# ProPrj___2025-03-19.net
KiCad netlist of a schematic drawn in EasyEDA Pro
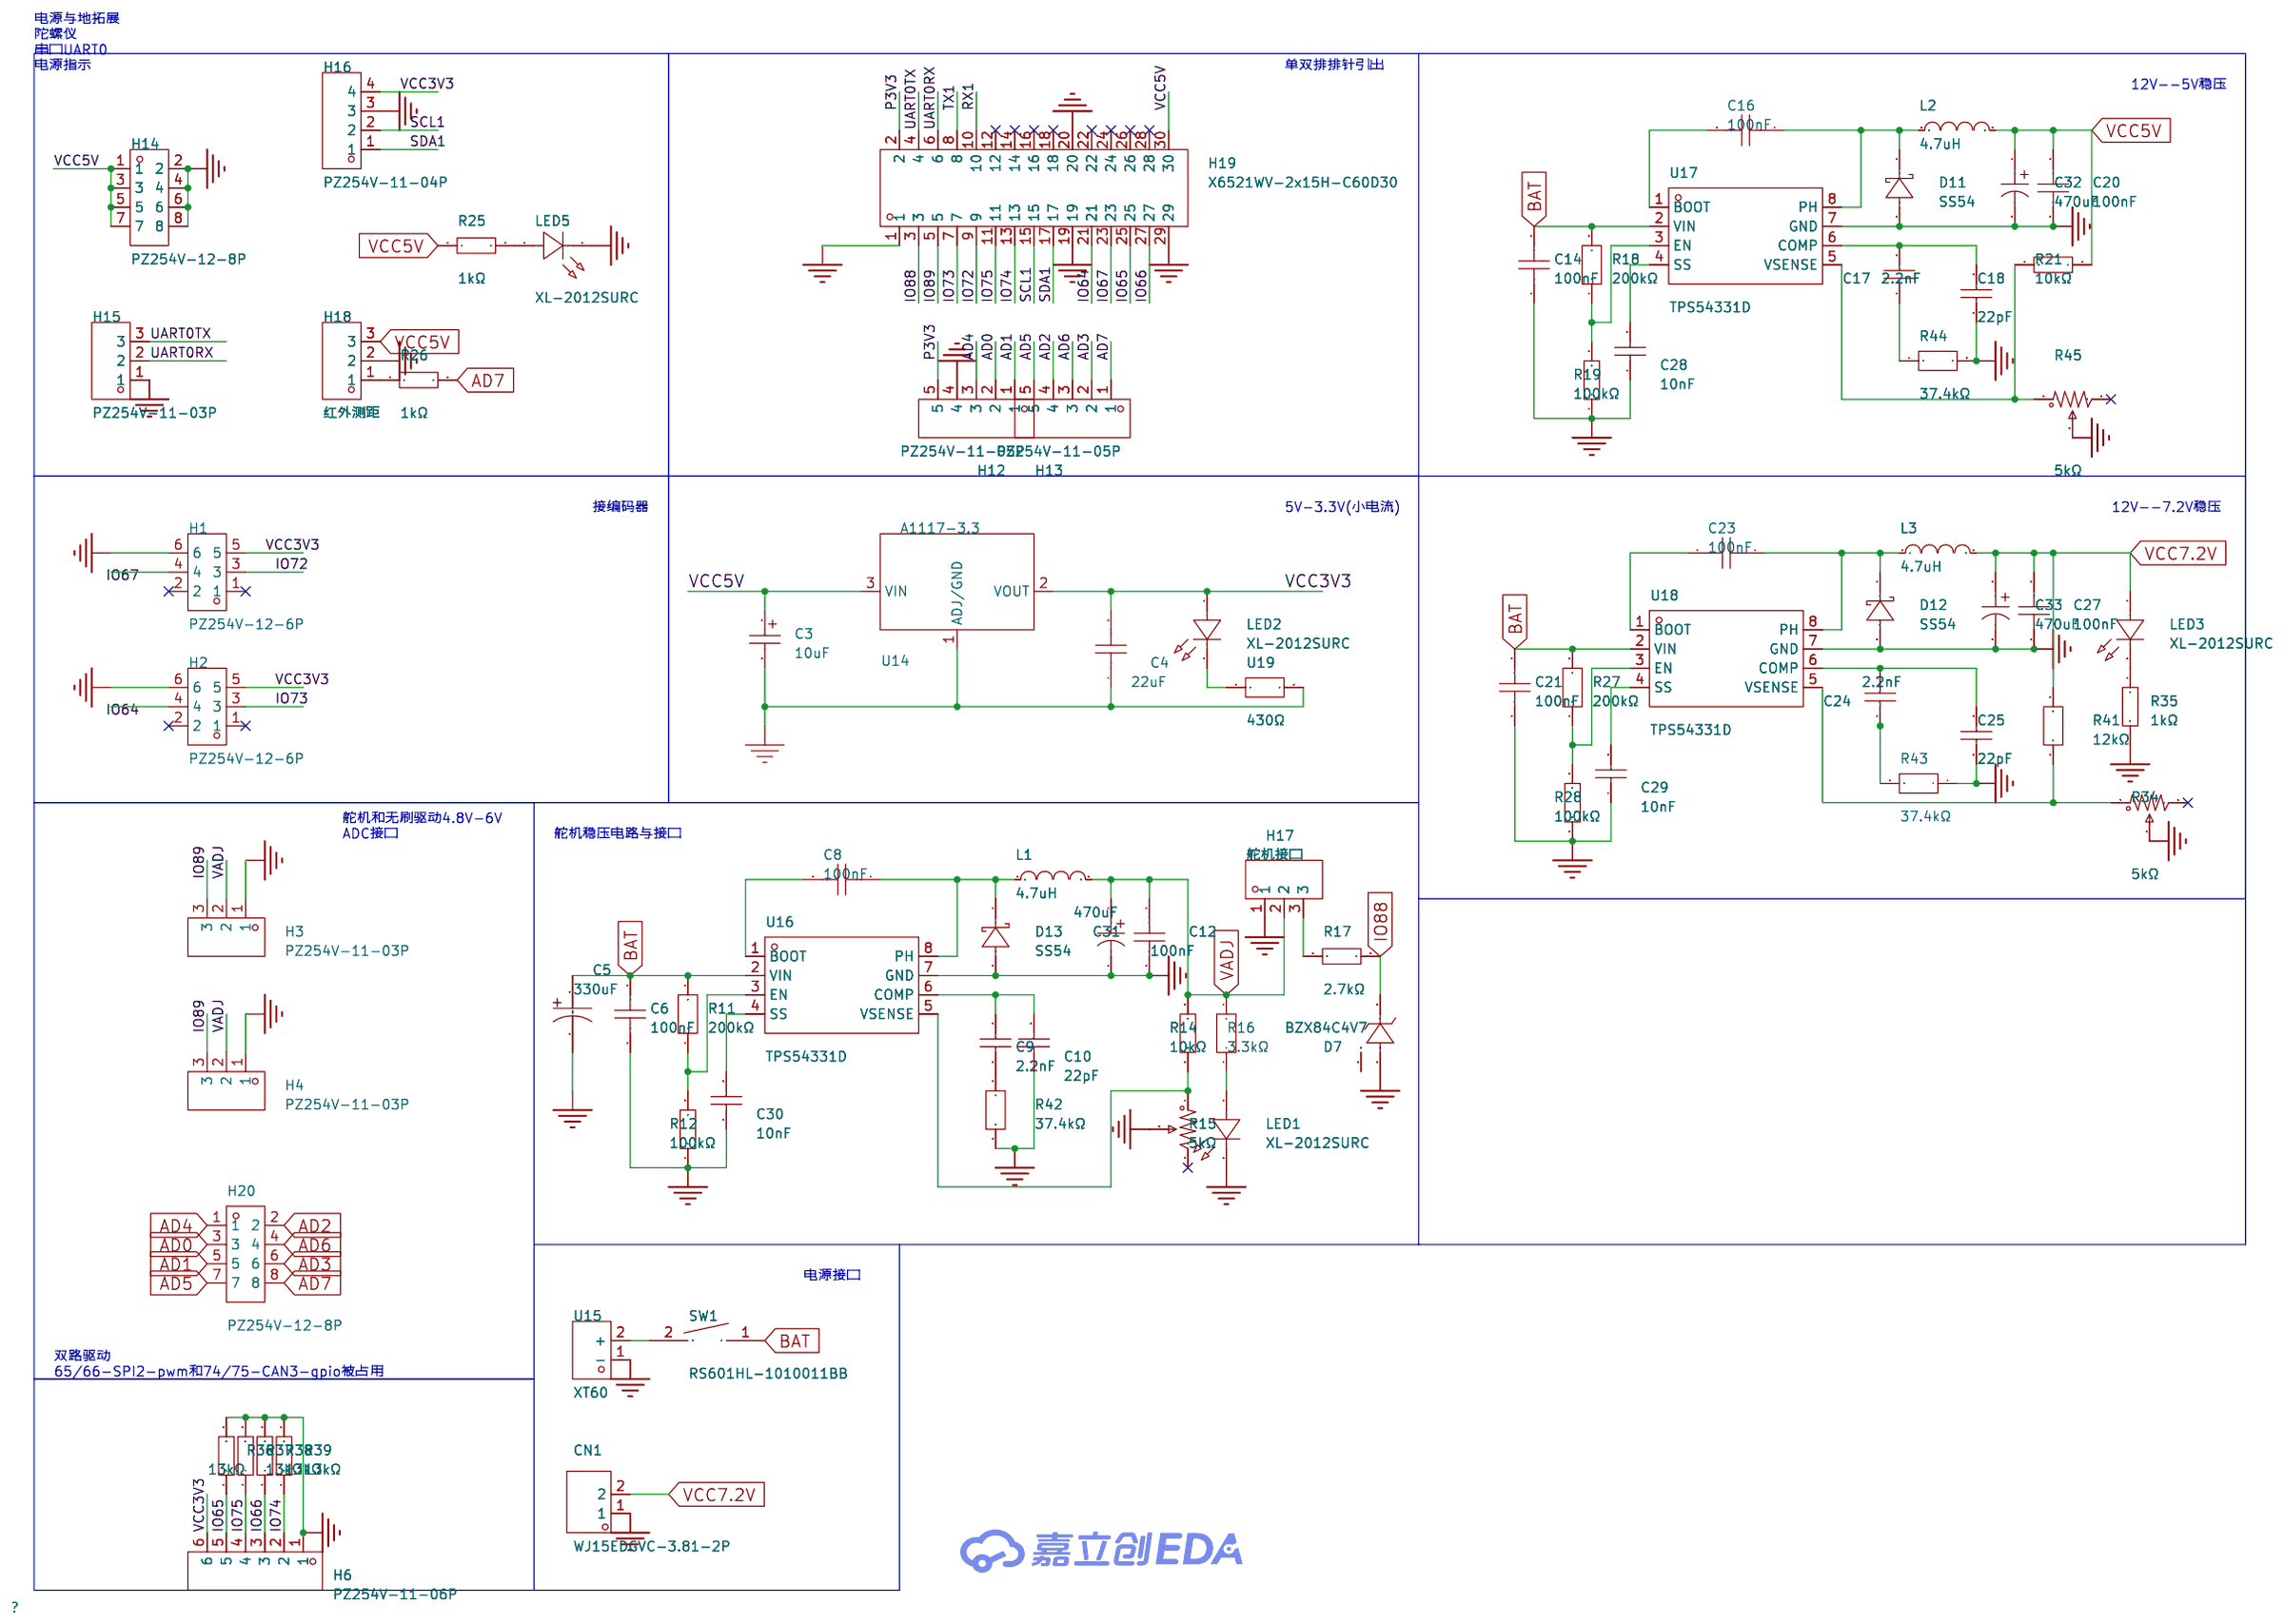
[diagram p0: schematic sheet]

(export (version "E")
  (design (tool "Eeschema 10.0.6"))
  (components
    (comp (ref "C3")
      (value "10uF")
      (footprint "easyedapro:CAP-SMD_L6.0-W3.2")
      (description "容值:10uF;精度:±10%;额定电压:16V;等效串联电阻:2Ω@100kHz;")
      (fields (field (name "Manufacturer Part") "TAJC106K016RNJ") (field (name "Manufacturer") "Kyocera AVX"))
      (libsource (lib "easyedapro") (part "TAJC106K016RNJ"))
    )
    (comp (ref "C4")
      (value "22uF")
      (footprint "easyedapro:C0805")
      (description "容值:22uF;精度:±20%;额定电压:35V;材质(温度系数):X5R;")
      (fields
        (field (name "Manufacturer Part") "CGA0805X5R226M350MT")
        (field (name "Manufacturer") "HRE(芯声)")
      )
      (libsource (lib "easyedapro") (part "CGA0805X5R226M350MT"))
    )
    (comp (ref "C5")
      (value "330uF")
      (footprint "easyedapro:CAP-SMD_BD8.0-L8.3-W8.3-LS9.3-FD-1")
      (description "容值:330uF;精度:±20%;额定电压:25V;纹波电流:228mA@120Hz;等效串联电阻(ESR):-;")
      (fields (field (name "Manufacturer Part") "RVT1E331M0810") (field (name "Manufacturer") "ROQANG(容强)"))
      (libsource (lib "easyedapro") (part "RVT1E331M0810_C335985"))
    )
    (comp (ref "C6")
      (value "100nF")
      (footprint "easyedapro:C0805")
      (description "容值:100nF;精度:±10%;额定电压:50V;材质(温度系数):X7R;")
      (fields
        (field (name "Manufacturer Part") "CC0805KRX7R9BB104")
        (field (name "Manufacturer") "YAGEO(国巨)")
      )
      (libsource (lib "easyedapro") (part "CC0805KRX7R9BB104"))
    )
    (comp (ref "C8")
      (value "100nF")
      (footprint "easyedapro:C0805")
      (description "容值:100nF;精度:±10%;额定电压:50V;材质(温度系数):X7R;")
      (fields
        (field (name "Manufacturer Part") "CC0805KRX7R9BB104")
        (field (name "Manufacturer") "YAGEO(国巨)")
      )
      (libsource (lib "easyedapro") (part "CC0805KRX7R9BB104"))
    )
    (comp (ref "C9")
      (value "2.2nF")
      (footprint "easyedapro:C0805")
      (description "容值:2.2nF;精度:±5%;额定电压:50V;材质(温度系数):C0G;")
      (fields
        (field (name "Manufacturer Part") "CL21C222JBFNNNE")
        (field (name "Manufacturer") "SAMSUNG(三星)")
      )
      (libsource (lib "easyedapro") (part "CL21C222JBFNNNE"))
    )
    (comp (ref "C10")
      (value "22pF")
      (footprint "easyedapro:C0603")
      (description "容值:22pF;精度:±5%;额定电压:50V;材质(温度系数):NP0;")
      (fields
        (field (name "Manufacturer Part") "CC0603JRNPO9BN220")
        (field (name "Manufacturer") "YAGEO(国巨)")
      )
      (libsource (lib "easyedapro") (part "CC0603JRNPO9BN220"))
    )
    (comp (ref "C12")
      (value "100nF")
      (footprint "easyedapro:C0805")
      (description "容值:100nF;精度:±10%;额定电压:50V;材质(温度系数):X7R;")
      (fields
        (field (name "Manufacturer Part") "CC0805KRX7R9BB104")
        (field (name "Manufacturer") "YAGEO(国巨)")
      )
      (libsource (lib "easyedapro") (part "CC0805KRX7R9BB104"))
    )
    (comp (ref "C14")
      (value "100nF")
      (footprint "easyedapro:C0805")
      (description "容值:100nF;精度:±10%;额定电压:50V;材质(温度系数):X7R;")
      (fields
        (field (name "Manufacturer Part") "CC0805KRX7R9BB104")
        (field (name "Manufacturer") "YAGEO(国巨)")
      )
      (libsource (lib "easyedapro") (part "CC0805KRX7R9BB104"))
    )
    (comp (ref "C16")
      (value "100nF")
      (footprint "easyedapro:C0805")
      (description "容值:100nF;精度:±10%;额定电压:50V;材质(温度系数):X7R;")
      (fields
        (field (name "Manufacturer Part") "CC0805KRX7R9BB104")
        (field (name "Manufacturer") "YAGEO(国巨)")
      )
      (libsource (lib "easyedapro") (part "CC0805KRX7R9BB104"))
    )
    (comp (ref "C17")
      (value "2.2nF")
      (footprint "easyedapro:C0805")
      (description "容值:2.2nF;精度:±5%;额定电压:50V;材质(温度系数):C0G;")
      (fields
        (field (name "Manufacturer Part") "CL21C222JBFNNNE")
        (field (name "Manufacturer") "SAMSUNG(三星)")
      )
      (libsource (lib "easyedapro") (part "CL21C222JBFNNNE"))
    )
    (comp (ref "C18")
      (value "22pF")
      (footprint "easyedapro:C0603")
      (description "容值:22pF;精度:±5%;额定电压:50V;材质(温度系数):NP0;")
      (fields
        (field (name "Manufacturer Part") "CC0603JRNPO9BN220")
        (field (name "Manufacturer") "YAGEO(国巨)")
      )
      (libsource (lib "easyedapro") (part "CC0603JRNPO9BN220"))
    )
    (comp (ref "C20")
      (value "100nF")
      (footprint "easyedapro:C0805")
      (description "容值:100nF;精度:±10%;额定电压:50V;材质(温度系数):X7R;")
      (fields
        (field (name "Manufacturer Part") "CC0805KRX7R9BB104")
        (field (name "Manufacturer") "YAGEO(国巨)")
      )
      (libsource (lib "easyedapro") (part "CC0805KRX7R9BB104"))
    )
    (comp (ref "C21")
      (value "100nF")
      (footprint "easyedapro:C0805")
      (description "容值:100nF;精度:±10%;额定电压:50V;材质(温度系数):X7R;")
      (fields
        (field (name "Manufacturer Part") "CC0805KRX7R9BB104")
        (field (name "Manufacturer") "YAGEO(国巨)")
      )
      (libsource (lib "easyedapro") (part "CC0805KRX7R9BB104"))
    )
    (comp (ref "C23")
      (value "100nF")
      (footprint "easyedapro:C0805")
      (description "容值:100nF;精度:±10%;额定电压:50V;材质(温度系数):X7R;")
      (fields
        (field (name "Manufacturer Part") "CC0805KRX7R9BB104")
        (field (name "Manufacturer") "YAGEO(国巨)")
      )
      (libsource (lib "easyedapro") (part "CC0805KRX7R9BB104"))
    )
    (comp (ref "C24")
      (value "2.2nF")
      (footprint "easyedapro:C0805")
      (description "容值:2.2nF;精度:±5%;额定电压:50V;材质(温度系数):C0G;")
      (fields
        (field (name "Manufacturer Part") "CL21C222JBFNNNE")
        (field (name "Manufacturer") "SAMSUNG(三星)")
      )
      (libsource (lib "easyedapro") (part "CL21C222JBFNNNE"))
    )
    (comp (ref "C25")
      (value "22pF")
      (footprint "easyedapro:C0603")
      (description "容值:22pF;精度:±5%;额定电压:50V;材质(温度系数):NP0;")
      (fields
        (field (name "Manufacturer Part") "CC0603JRNPO9BN220")
        (field (name "Manufacturer") "YAGEO(国巨)")
      )
      (libsource (lib "easyedapro") (part "CC0603JRNPO9BN220"))
    )
    (comp (ref "C27")
      (value "100nF")
      (footprint "easyedapro:C0805")
      (description "容值:100nF;精度:±10%;额定电压:50V;材质(温度系数):X7R;")
      (fields
        (field (name "Manufacturer Part") "CC0805KRX7R9BB104")
        (field (name "Manufacturer") "YAGEO(国巨)")
      )
      (libsource (lib "easyedapro") (part "CC0805KRX7R9BB104"))
    )
    (comp (ref "C28")
      (value "10nF")
      (footprint "easyedapro:C0805")
      (description "容值:10nF;精度:±10%;额定电压:50V;材质(温度系数):X7R;")
      (fields
        (field (name "Manufacturer Part") "CL21B103KBANNNC")
        (field (name "Manufacturer") "SAMSUNG(三星)")
      )
      (libsource (lib "easyedapro") (part "CL21B103KBANNNC"))
    )
    (comp (ref "C29")
      (value "10nF")
      (footprint "easyedapro:C0805")
      (description "容值:10nF;精度:±10%;额定电压:50V;材质(温度系数):X7R;")
      (fields
        (field (name "Manufacturer Part") "CL21B103KBANNNC")
        (field (name "Manufacturer") "SAMSUNG(三星)")
      )
      (libsource (lib "easyedapro") (part "CL21B103KBANNNC"))
    )
    (comp (ref "C30")
      (value "10nF")
      (footprint "easyedapro:C0805")
      (description "容值:10nF;精度:±10%;额定电压:50V;材质(温度系数):X7R;")
      (fields
        (field (name "Manufacturer Part") "CL21B103KBANNNC")
        (field (name "Manufacturer") "SAMSUNG(三星)")
      )
      (libsource (lib "easyedapro") (part "CL21B103KBANNNC"))
    )
    (comp (ref "C31")
      (value "470uF")
      (footprint "easyedapro:CAP-SMD_BD8.0-L8.3-W8.3-LS8.9-FD")
      (description "容值:470uF;精度:±20%;额定电压:16V;纹波电流:240mA@120Hz;")
      (fields (field (name "Manufacturer Part") "CK1C471M-CRF10") (field (name "Manufacturer") "ROQANG(容强)"))
      (libsource (lib "easyedapro") (part "CK1C471M-CRF10_C5162359"))
    )
    (comp (ref "C32")
      (value "470uF")
      (footprint "easyedapro:CAP-SMD_BD8.0-L8.3-W8.3-LS8.9-FD")
      (description "容值:470uF;精度:±20%;额定电压:16V;纹波电流:240mA@120Hz;")
      (fields (field (name "Manufacturer Part") "CK1C471M-CRF10") (field (name "Manufacturer") "ROQANG(容强)"))
      (libsource (lib "easyedapro") (part "CK1C471M-CRF10_C5162359"))
    )
    (comp (ref "C33")
      (value "470uF")
      (footprint "easyedapro:CAP-SMD_BD8.0-L8.3-W8.3-LS8.9-FD")
      (description "容值:470uF;精度:±20%;额定电压:16V;纹波电流:240mA@120Hz;")
      (fields (field (name "Manufacturer Part") "CK1C471M-CRF10") (field (name "Manufacturer") "ROQANG(容强)"))
      (libsource (lib "easyedapro") (part "CK1C471M-CRF10_C5162359"))
    )
    (comp (ref "CN1")
      (value "WJ15EDGVC-3.81-2P")
      (footprint "easyedapro:CONN-TH_WJ15EDGVC-3.81-2P")
      (fields (field (name "Manufacturer") "KANGNEX(康奈克斯电气)"))
      (libsource (lib "easyedapro") (part "WJ15EDGVC-3.81-2P"))
    )
    (comp (ref "D7")
      (value "BZX84C4V7")
      (footprint "easyedapro:SOT-23-3_L2.9-W1.3-P1.90-LS2.4-BR")
      (description "二极管配置:独立式;稳压值(标称值):4.7V;稳压值(范围):4.4V~5V;耗散功率(Pd):350mW;")
      (fields (field (name "Manufacturer") "LGE(鲁光)"))
      (libsource (lib "easyedapro") (part "BZX84C4V7_C841158"))
    )
    (comp (ref "D11")
      (value "SS54")
      (footprint "easyedapro:SMA_L4.3-W2.6-LS5.0-RD")
      (description "二极管配置:独立式;正向压降(Vf):550mV@5A;直流反向耐压(Vr):40V;整流电流:5A;")
      (fields (field (name "Manufacturer") "TWGMC(台湾迪嘉)"))
      (libsource (lib "easyedapro") (part "SS54_C727065"))
    )
    (comp (ref "D12")
      (value "SS54")
      (footprint "easyedapro:SMA_L4.3-W2.6-LS5.0-RD")
      (description "二极管配置:独立式;正向压降(Vf):550mV@5A;直流反向耐压(Vr):40V;整流电流:5A;")
      (fields (field (name "Manufacturer") "TWGMC(台湾迪嘉)"))
      (libsource (lib "easyedapro") (part "SS54_C727065"))
    )
    (comp (ref "D13")
      (value "SS54")
      (footprint "easyedapro:SMA_L4.3-W2.6-LS5.0-RD")
      (description "二极管配置:独立式;正向压降(Vf):550mV@5A;直流反向耐压(Vr):40V;整流电流:5A;")
      (fields (field (name "Manufacturer") "TWGMC(台湾迪嘉)"))
      (libsource (lib "easyedapro") (part "SS54_C727065"))
    )
    (comp (ref "H1")
      (value "PZ254V-12-6P")
      (footprint "easyedapro:HDR-TH_6P-P2.54-V-M-R2-C3-S2.54")
      (fields (field (name "Manufacturer") "XFCN(兴飞)"))
      (libsource (lib "easyedapro") (part "PZ254V-12-6P"))
    )
    (comp (ref "H2")
      (value "PZ254V-12-6P")
      (footprint "easyedapro:HDR-TH_6P-P2.54-V-M-R2-C3-S2.54")
      (fields (field (name "Manufacturer") "XFCN(兴飞)"))
      (libsource (lib "easyedapro") (part "PZ254V-12-6P"))
    )
    (comp (ref "H3")
      (value "PZ254V-11-03P")
      (footprint "easyedapro:HDR-TH_3P-P2.54-V-M")
      (fields (field (name "Manufacturer") "XFCN(兴飞)"))
      (libsource (lib "easyedapro") (part "PZ254V-11-03P_C2937625"))
    )
    (comp (ref "H4")
      (value "PZ254V-11-03P")
      (footprint "easyedapro:HDR-TH_3P-P2.54-V-M")
      (fields (field (name "Manufacturer") "XFCN(兴飞)"))
      (libsource (lib "easyedapro") (part "PZ254V-11-03P_C2937625"))
    )
    (comp (ref "H6")
      (value "PZ254V-11-06P")
      (footprint "easyedapro:HDR-TH_6P-P2.54-V-M")
      (fields (field (name "Manufacturer") "XFCN(兴飞)"))
      (libsource (lib "easyedapro") (part "PZ254V-11-06P"))
    )
    (comp (ref "H12")
      (value "PZ254V-11-05P")
      (footprint "easyedapro:HDR-TH_5P-P2.54-V-M")
      (fields (field (name "Manufacturer") "XFCN(兴飞)"))
      (libsource (lib "easyedapro") (part "PZ254V-11-05P"))
    )
    (comp (ref "H13")
      (value "PZ254V-11-05P")
      (footprint "easyedapro:HDR-TH_5P-P2.54-V-M")
      (fields (field (name "Manufacturer") "XFCN(兴飞)"))
      (libsource (lib "easyedapro") (part "PZ254V-11-05P"))
    )
    (comp (ref "H14")
      (value "PZ254V-12-8P")
      (footprint "easyedapro:HDR-TH_8P-P2.54-V-M-R2-C4-S2.54")
      (fields (field (name "Manufacturer") "XFCN(兴飞)"))
      (libsource (lib "easyedapro") (part "PZ254V-12-8P"))
    )
    (comp (ref "H15")
      (value "PZ254V-11-03P")
      (footprint "easyedapro:HDR-TH_3P-P2.54-V-M")
      (fields (field (name "Manufacturer") "XFCN(兴飞)"))
      (libsource (lib "easyedapro") (part "PZ254V-11-03P_C2937625"))
    )
    (comp (ref "H16")
      (value "PZ254V-11-04P")
      (footprint "easyedapro:HDR-TH_4P-P2.54-V-M")
      (fields (field (name "Manufacturer") "XFCN(兴飞)"))
      (libsource (lib "easyedapro") (part "PZ254V-11-04P_C2691448"))
    )
    (comp (ref "H17")
      (value "舵机接口")
      (footprint "easyedapro:HDR-TH_3P-P2.54-V-M")
      (fields (field (name "Manufacturer") "XFCN(兴飞)"))
      (libsource (lib "easyedapro") (part "PZ254V-11-03P_C2937625"))
    )
    (comp (ref "H18")
      (value "红外测距")
      (footprint "easyedapro:HDR-TH_3P-P2.54-V-M")
      (fields (field (name "Manufacturer") "XFCN(兴飞)"))
      (libsource (lib "easyedapro") (part "PZ254V-11-03P_C2937625"))
    )
    (comp (ref "H19")
      (value "X6521WV-2x15H-C60D30")
      (footprint "easyedapro:HDR-TH_30P-P2.54-V-M-R2-C15-S2.54-BL")
      (fields (field (name "Manufacturer") "XKB Connection(中国星坤)"))
      (libsource (lib "easyedapro") (part "X6521WV-2×15H-C30D60"))
    )
    (comp (ref "H20")
      (value "PZ254V-12-8P")
      (footprint "easyedapro:HDR-TH_8P-P2.54-V-M-R2-C4-S2.54")
      (fields (field (name "Manufacturer") "XFCN(兴飞)"))
      (libsource (lib "easyedapro") (part "PZ254V-12-8P"))
    )
    (comp (ref "L1")
      (value "4.7uH")
      (footprint "easyedapro:IND-SMD_L7.3-W6.6_MHCI06030")
      (description "电感值:4.7uH;精度:±20%;额定电流:5.5A;")
      (fields
        (field (name "Manufacturer Part") "SLO0630H4R7MTT")
        (field (name "Manufacturer") "Sunltech(韩国顺磁)")
      )
      (libsource (lib "easyedapro") (part "SLO0630H4R7MTT"))
    )
    (comp (ref "L2")
      (value "4.7uH")
      (footprint "easyedapro:IND-SMD_L7.3-W6.6_MHCI06030")
      (description "电感值:4.7uH;精度:±20%;额定电流:5.5A;")
      (fields
        (field (name "Manufacturer Part") "SLO0630H4R7MTT")
        (field (name "Manufacturer") "Sunltech(韩国顺磁)")
      )
      (libsource (lib "easyedapro") (part "SLO0630H4R7MTT"))
    )
    (comp (ref "L3")
      (value "4.7uH")
      (footprint "easyedapro:IND-SMD_L7.3-W6.6_MHCI06030")
      (description "电感值:4.7uH;精度:±20%;额定电流:5.5A;")
      (fields
        (field (name "Manufacturer Part") "SLO0630H4R7MTT")
        (field (name "Manufacturer") "Sunltech(韩国顺磁)")
      )
      (libsource (lib "easyedapro") (part "SLO0630H4R7MTT"))
    )
    (comp (ref "LED1")
      (value "XL-2012SURC")
      (footprint "easyedapro:LED0805-R-RD")
      (description "发光颜色:红色;功率:55mW;正向电流:25mA;主波长:617nm~621nm;透镜颜色:无色透明透镜;色温:-;发光角度:120°;载带方式:正贴;工作温度:-30°C~+85°C;")
      (fields (field (name "Manufacturer") "XINGLIGHT(成兴光)"))
      (libsource (lib "easyedapro") (part "XL-2012SURC"))
    )
    (comp (ref "LED2")
      (value "XL-2012SURC")
      (footprint "easyedapro:LED0805-R-RD")
      (description "发光颜色:红色;功率:55mW;正向电流:25mA;主波长:617nm~621nm;透镜颜色:无色透明透镜;色温:-;发光角度:120°;载带方式:正贴;工作温度:-30°C~+85°C;")
      (fields (field (name "Manufacturer") "XINGLIGHT(成兴光)"))
      (libsource (lib "easyedapro") (part "XL-2012SURC"))
    )
    (comp (ref "LED3")
      (value "XL-2012SURC")
      (footprint "easyedapro:LED0805-R-RD")
      (description "发光颜色:红色;功率:55mW;正向电流:25mA;主波长:617nm~621nm;透镜颜色:无色透明透镜;色温:-;发光角度:120°;载带方式:正贴;工作温度:-30°C~+85°C;")
      (fields (field (name "Manufacturer") "XINGLIGHT(成兴光)"))
      (libsource (lib "easyedapro") (part "XL-2012SURC"))
    )
    (comp (ref "LED5")
      (value "XL-2012SURC")
      (footprint "easyedapro:LED0805-R-RD")
      (description "发光颜色:红色;功率:55mW;正向电流:25mA;主波长:617nm~621nm;透镜颜色:无色透明透镜;色温:-;发光角度:120°;载带方式:正贴;工作温度:-30°C~+85°C;")
      (fields (field (name "Manufacturer") "XINGLIGHT(成兴光)"))
      (libsource (lib "easyedapro") (part "XL-2012SURC"))
    )
    (comp (ref "R11")
      (value "200kΩ")
      (footprint "easyedapro:R0603")
      (description "电阻类型:厚膜电阻;阻值:200kΩ;精度:±1%;功率:100mW;工作电压:75V;温度系数:±100ppm/°C;")
      (fields (field (name "Manufacturer Part") "FRC0603F2003TS") (field (name "Manufacturer") "FOJAN(富捷)"))
      (libsource (lib "easyedapro") (part "FRC0603F2003TS"))
    )
    (comp (ref "R12")
      (value "100kΩ")
      (footprint "easyedapro:R0805")
      (description "电阻类型:厚膜电阻;阻值:100kΩ;精度:±1%;功率:125mW;最大工作电压:150V;温度系数:±100ppm/°C;")
      (fields
        (field (name "Manufacturer Part") "0805W8F1003T5E")
        (field (name "Manufacturer") "UNI-ROYAL(厚声)")
      )
      (libsource (lib "easyedapro") (part "0805W8F1003T5E_C149504"))
    )
    (comp (ref "R14")
      (value "10kΩ")
      (footprint "easyedapro:R0805")
      (description "电阻类型:厚膜电阻;阻值:10kΩ;精度:±1%;功率:125mW;最大工作电压:150V;温度系数:±100ppm/°C;")
      (fields
        (field (name "Manufacturer Part") "0805W8F1002T5E")
        (field (name "Manufacturer") "UNI-ROYAL(厚声)")
      )
      (libsource (lib "easyedapro") (part "0805W8F1002T5E"))
    )
    (comp (ref "R15")
      (value "5kΩ")
      (footprint "easyedapro:RES-ADJ-TH_3P-L6.8-W4.6-P2.50-TL-BS-3266X")
      (description "阻值:5kΩ;精度:±10%;功率:250mW;温度系数:±100ppm/°C;")
      (fields (field (name "Manufacturer Part") "3266X-1-502LF") (field (name "Manufacturer") "BOURNS"))
      (libsource (lib "easyedapro") (part "3266X-1-502LF"))
    )
    (comp (ref "R16")
      (value "3.3kΩ")
      (footprint "easyedapro:R0805")
      (description "电阻类型:厚膜电阻;阻值:3.3kΩ;精度:±1%;功率:125mW;最大工作电压:150V;温度系数:±100ppm/°C;")
      (fields (field (name "Manufacturer Part") "FRC0805F3301TS") (field (name "Manufacturer") "FOJAN(富捷)"))
      (libsource (lib "easyedapro") (part "FRC0805F3301TS"))
    )
    (comp (ref "R17")
      (value "2.7kΩ")
      (footprint "easyedapro:R0603")
      (description "电阻类型:厚膜电阻;阻值:2.7kΩ;精度:±1%;功率:100mW;最大工作电压:75V;温度系数:±100ppm/°C;")
      (fields
        (field (name "Manufacturer Part") "0603WAF2701T5E")
        (field (name "Manufacturer") "UNI-ROYAL(厚声)")
      )
      (libsource (lib "easyedapro") (part "0603WAF2701T5E"))
    )
    (comp (ref "R18")
      (value "200kΩ")
      (footprint "easyedapro:R0603")
      (description "电阻类型:厚膜电阻;阻值:200kΩ;精度:±1%;功率:100mW;工作电压:75V;温度系数:±100ppm/°C;")
      (fields (field (name "Manufacturer Part") "FRC0603F2003TS") (field (name "Manufacturer") "FOJAN(富捷)"))
      (libsource (lib "easyedapro") (part "FRC0603F2003TS"))
    )
    (comp (ref "R19")
      (value "100kΩ")
      (footprint "easyedapro:R0805")
      (description "电阻类型:厚膜电阻;阻值:100kΩ;精度:±1%;功率:125mW;最大工作电压:150V;温度系数:±100ppm/°C;")
      (fields
        (field (name "Manufacturer Part") "0805W8F1003T5E")
        (field (name "Manufacturer") "UNI-ROYAL(厚声)")
      )
      (libsource (lib "easyedapro") (part "0805W8F1003T5E_C149504"))
    )
    (comp (ref "R21")
      (value "10kΩ")
      (footprint "easyedapro:R0805")
      (description "电阻类型:厚膜电阻;阻值:10kΩ;精度:±1%;功率:125mW;最大工作电压:150V;温度系数:±100ppm/°C;")
      (fields
        (field (name "Manufacturer Part") "0805W8F1002T5E")
        (field (name "Manufacturer") "UNI-ROYAL(厚声)")
      )
      (libsource (lib "easyedapro") (part "0805W8F1002T5E"))
    )
    (comp (ref "R25")
      (value "1kΩ")
      (footprint "easyedapro:R0603")
      (description "电阻类型:厚膜电阻;阻值:1kΩ;精度:±1%;功率:100mW;最大工作电压:75V;温度系数:±100ppm/°C;")
      (fields
        (field (name "Manufacturer Part") "0603WAF1001T5E")
        (field (name "Manufacturer") "UNI-ROYAL(厚声)")
      )
      (libsource (lib "easyedapro") (part "0603WAF1001T5E"))
    )
    (comp (ref "R26")
      (value "1kΩ")
      (footprint "easyedapro:R0603")
      (description "电阻类型:厚膜电阻;阻值:1kΩ;精度:±1%;功率:100mW;最大工作电压:75V;温度系数:±100ppm/°C;")
      (fields
        (field (name "Manufacturer Part") "0603WAF1001T5E")
        (field (name "Manufacturer") "UNI-ROYAL(厚声)")
      )
      (libsource (lib "easyedapro") (part "0603WAF1001T5E"))
    )
    (comp (ref "R27")
      (value "200kΩ")
      (footprint "easyedapro:R0603")
      (description "电阻类型:厚膜电阻;阻值:200kΩ;精度:±1%;功率:100mW;工作电压:75V;温度系数:±100ppm/°C;")
      (fields (field (name "Manufacturer Part") "FRC0603F2003TS") (field (name "Manufacturer") "FOJAN(富捷)"))
      (libsource (lib "easyedapro") (part "FRC0603F2003TS"))
    )
    (comp (ref "R28")
      (value "100kΩ")
      (footprint "easyedapro:R0805")
      (description "电阻类型:厚膜电阻;阻值:100kΩ;精度:±1%;功率:125mW;最大工作电压:150V;温度系数:±100ppm/°C;")
      (fields
        (field (name "Manufacturer Part") "0805W8F1003T5E")
        (field (name "Manufacturer") "UNI-ROYAL(厚声)")
      )
      (libsource (lib "easyedapro") (part "0805W8F1003T5E_C149504"))
    )
    (comp (ref "R34")
      (value "5kΩ")
      (footprint "easyedapro:RES-ADJ-TH_3P-L6.8-W4.6-P2.50-TL-BS-3266X")
      (description "阻值:5kΩ;精度:±10%;功率:250mW;温度系数:±100ppm/°C;")
      (fields (field (name "Manufacturer Part") "3266X-1-502LF") (field (name "Manufacturer") "BOURNS"))
      (libsource (lib "easyedapro") (part "3266X-1-502LF"))
    )
    (comp (ref "R35")
      (value "1kΩ")
      (footprint "easyedapro:R0603")
      (description "电阻类型:厚膜电阻;阻值:510Ω;精度:±1%;功率:100mW;最大工作电压:75V;温度系数:±100ppm/°C;")
      (fields
        (field (name "Manufacturer Part") "0603WAF5100T5E")
        (field (name "Manufacturer") "UNI-ROYAL(厚声)")
      )
      (libsource (lib "easyedapro") (part "0603WAF5100T5E"))
    )
    (comp (ref "R36")
      (value "13kΩ")
      (footprint "easyedapro:R0805")
      (description "电阻类型:厚膜电阻;阻值:13kΩ;精度:±1%;功率:125mW;最大工作电压:150V;温度系数:±100ppm/°C;")
      (fields
        (field (name "Manufacturer Part") "0805W8F1302T5E")
        (field (name "Manufacturer") "UNI-ROYAL(厚声)")
      )
      (libsource (lib "easyedapro") (part "0805W8F1302T5E"))
    )
    (comp (ref "R37")
      (value "13kΩ")
      (footprint "easyedapro:R0805")
      (description "电阻类型:厚膜电阻;阻值:13kΩ;精度:±1%;功率:125mW;最大工作电压:150V;温度系数:±100ppm/°C;")
      (fields
        (field (name "Manufacturer Part") "0805W8F1302T5E")
        (field (name "Manufacturer") "UNI-ROYAL(厚声)")
      )
      (libsource (lib "easyedapro") (part "0805W8F1302T5E"))
    )
    (comp (ref "R38")
      (value "13kΩ")
      (footprint "easyedapro:R0805")
      (description "电阻类型:厚膜电阻;阻值:13kΩ;精度:±1%;功率:125mW;最大工作电压:150V;温度系数:±100ppm/°C;")
      (fields
        (field (name "Manufacturer Part") "0805W8F1302T5E")
        (field (name "Manufacturer") "UNI-ROYAL(厚声)")
      )
      (libsource (lib "easyedapro") (part "0805W8F1302T5E"))
    )
    (comp (ref "R39")
      (value "13kΩ")
      (footprint "easyedapro:R0805")
      (description "电阻类型:厚膜电阻;阻值:13kΩ;精度:±1%;功率:125mW;最大工作电压:150V;温度系数:±100ppm/°C;")
      (fields
        (field (name "Manufacturer Part") "0805W8F1302T5E")
        (field (name "Manufacturer") "UNI-ROYAL(厚声)")
      )
      (libsource (lib "easyedapro") (part "0805W8F1302T5E"))
    )
    (comp (ref "R41")
      (value "12kΩ")
      (footprint "easyedapro:R0805")
      (description "电阻类型:厚膜电阻;阻值:12kΩ;精度:±1%;功率:125mW;最大工作电压:150V;温度系数:±100ppm/°C;")
      (fields (field (name "Manufacturer Part") "FRC0805F1202TS") (field (name "Manufacturer") "FOJAN(富捷)"))
      (libsource (lib "easyedapro") (part "FRC0805F1202TS"))
    )
    (comp (ref "R42")
      (value "37.4kΩ")
      (footprint "easyedapro:R0603")
      (description "电阻类型:薄膜电阻;阻值:37kΩ;精度:±0.25%;功率:100mW;最大工作电压:75V;温度系数:±25ppm/°C;")
      (fields (field (name "Manufacturer Part") "RN73R1JTTD3702C25") (field (name "Manufacturer") "KOA"))
      (libsource (lib "easyedapro") (part "RN73R1JTTD3702C25"))
    )
    (comp (ref "R43")
      (value "37.4kΩ")
      (footprint "easyedapro:R0603")
      (description "电阻类型:薄膜电阻;阻值:37kΩ;精度:±0.25%;功率:100mW;最大工作电压:75V;温度系数:±25ppm/°C;")
      (fields (field (name "Manufacturer Part") "RN73R1JTTD3702C25") (field (name "Manufacturer") "KOA"))
      (libsource (lib "easyedapro") (part "RN73R1JTTD3702C25"))
    )
    (comp (ref "R44")
      (value "37.4kΩ")
      (footprint "easyedapro:R0603")
      (description "电阻类型:薄膜电阻;阻值:37kΩ;精度:±0.25%;功率:100mW;最大工作电压:75V;温度系数:±25ppm/°C;")
      (fields (field (name "Manufacturer Part") "RN73R1JTTD3702C25") (field (name "Manufacturer") "KOA"))
      (libsource (lib "easyedapro") (part "RN73R1JTTD3702C25"))
    )
    (comp (ref "R45")
      (value "5kΩ")
      (footprint "easyedapro:RES-ADJ-TH_3P-L6.8-W4.6-P2.50-TL-BS-3266X")
      (description "阻值:5kΩ;精度:±10%;功率:250mW;温度系数:±100ppm/°C;")
      (fields (field (name "Manufacturer Part") "3266X-1-502LF") (field (name "Manufacturer") "BOURNS"))
      (libsource (lib "easyedapro") (part "3266X-1-502LF"))
    )
    (comp (ref "SW1")
      (value "RS601HL-1010011BB")
      (footprint "easyedapro:SW-TH_RS601HL-1010011BB")
      (description "带灯:无;引脚样式:焊片;额定电流:3A;额定电压(AC):250V;额定电压(DC):-;电路结构:单刀单掷;机械寿命:1万次;")
      (fields (field (name "Manufacturer") "HCTL(华灿天禄)"))
      (libsource (lib "easyedapro") (part "RS601HL-1010011BB"))
    )
    (comp (ref "U14")
      (value "A1117-3.3")
      (footprint "easyedapro:asm1117")
      (fields (field (name "Manufacturer") "IDCHIP(英锐芯)"))
      (libsource (lib "easyedapro") (part "A1117-3.3"))
    )
    (comp (ref "U15")
      (value "XT60")
      (footprint "easyedapro:CONN-TH_XT60")
      (description "类别:-;类型1:-;")
      (fields (field (name "Manufacturer") "AMASS(艾迈斯)"))
      (libsource (lib "easyedapro") (part "XT60"))
    )
    (comp (ref "U16")
      (value "TPS54331D")
      (footprint "easyedapro:SOIC-8_L4.9-W3.9-P1.27-LS6.0-BL")
      (description "功能类型:降压型;输出类型:可调;输入电压:3.5V~28V;输出电压:-;输出电流:3A;")
      (fields (field (name "Manufacturer") "TI(德州仪器)"))
      (libsource (lib "easyedapro") (part "TPS54331D"))
    )
    (comp (ref "U17")
      (value "TPS54331D")
      (footprint "easyedapro:SOIC-8_L4.9-W3.9-P1.27-LS6.0-BL")
      (description "功能类型:降压型;输出类型:可调;输入电压:3.5V~28V;输出电压:-;输出电流:3A;")
      (fields (field (name "Manufacturer") "TI(德州仪器)"))
      (libsource (lib "easyedapro") (part "TPS54331D"))
    )
    (comp (ref "U18")
      (value "TPS54331D")
      (footprint "easyedapro:SOIC-8_L4.9-W3.9-P1.27-LS6.0-BL")
      (description "功能类型:降压型;输出类型:可调;输入电压:3.5V~28V;输出电压:-;输出电流:3A;")
      (fields (field (name "Manufacturer") "TI(德州仪器)"))
      (libsource (lib "easyedapro") (part "TPS54331D"))
    )
    (comp (ref "U19")
      (value "430Ω")
      (footprint "easyedapro:R0805")
      (description "电阻类型:厚膜电阻;阻值:430Ω;精度:±1%;功率:125mW;最大工作电压:150V;温度系数:±100ppm/°C;")
      (fields (field (name "Manufacturer Part") "FRC0805F4300TS") (field (name "Manufacturer") "FOJAN(富捷)"))
      (libsource (lib "easyedapro") (part "FRC0805F4300TS"))
    )
  )
  (nets
    (net (code "1") (name "/IO64") (class "Default")
      (node (ref "H19") (pin "21") (pinfunction "21_21") (pintype "unspecified"))
      (node (ref "H2") (pin "4") (pinfunction "4_4") (pintype "unspecified"))
    )
    (net (code "2") (name "/IO65") (class "Default")
      (node (ref "H19") (pin "25") (pinfunction "25_25") (pintype "unspecified"))
      (node (ref "H6") (pin "5") (pinfunction "5_5") (pintype "unspecified"))
      (node (ref "R36") (pin "1") (pinfunction "1_1") (pintype "input"))
    )
    (net (code "3") (name "/IO66") (class "Default")
      (node (ref "H19") (pin "27") (pinfunction "27_27") (pintype "unspecified"))
      (node (ref "H6") (pin "3") (pinfunction "3_3") (pintype "unspecified"))
      (node (ref "R38") (pin "1") (pinfunction "1_1") (pintype "input"))
    )
    (net (code "4") (name "/IO67") (class "Default")
      (node (ref "H1") (pin "4") (pinfunction "4_4") (pintype "unspecified"))
      (node (ref "H19") (pin "23") (pinfunction "23_23") (pintype "unspecified"))
    )
    (net (code "5") (name "/IO72") (class "Default")
      (node (ref "H1") (pin "3") (pinfunction "3_3") (pintype "unspecified"))
      (node (ref "H19") (pin "9") (pinfunction "9_9") (pintype "unspecified"))
    )
    (net (code "6") (name "/IO73") (class "Default")
      (node (ref "H19") (pin "7") (pinfunction "7_7") (pintype "unspecified"))
      (node (ref "H2") (pin "3") (pinfunction "3_3") (pintype "unspecified"))
    )
    (net (code "7") (name "/IO74") (class "Default")
      (node (ref "H19") (pin "13") (pinfunction "13_13") (pintype "unspecified"))
      (node (ref "H6") (pin "2") (pinfunction "2_2") (pintype "unspecified"))
      (node (ref "R39") (pin "1") (pinfunction "1_1") (pintype "input"))
    )
    (net (code "8") (name "/IO75") (class "Default")
      (node (ref "H19") (pin "11") (pinfunction "11_11") (pintype "unspecified"))
      (node (ref "H6") (pin "4") (pinfunction "4_4") (pintype "unspecified"))
      (node (ref "R37") (pin "1") (pinfunction "1_1") (pintype "input"))
    )
    (net (code "9") (name "/IO89") (class "Default")
      (node (ref "H19") (pin "5") (pinfunction "5_5") (pintype "unspecified"))
      (node (ref "H3") (pin "3") (pinfunction "3_3") (pintype "unspecified"))
      (node (ref "H4") (pin "3") (pinfunction "3_3") (pintype "unspecified"))
    )
    (net (code "10") (name "/P3V3") (class "Default")
      (node (ref "H12") (pin "5") (pinfunction "5_5") (pintype "unspecified"))
      (node (ref "H19") (pin "2") (pinfunction "2_2") (pintype "unspecified"))
    )
    (net (code "11") (name "/RX1") (class "Default")
      (node (ref "H19") (pin "10") (pinfunction "10_10") (pintype "unspecified"))
    )
    (net (code "12") (name "/SCL1") (class "Default")
      (node (ref "H16") (pin "2") (pinfunction "2_2") (pintype "unspecified"))
      (node (ref "H19") (pin "15") (pinfunction "15_15") (pintype "unspecified"))
    )
    (net (code "13") (name "/SDA1") (class "Default")
      (node (ref "H16") (pin "1") (pinfunction "1_1") (pintype "unspecified"))
      (node (ref "H19") (pin "17") (pinfunction "17_17") (pintype "unspecified"))
    )
    (net (code "14") (name "/TX1") (class "Default")
      (node (ref "H19") (pin "8") (pinfunction "8_8") (pintype "unspecified"))
    )
    (net (code "15") (name "/UART0RX") (class "Default")
      (node (ref "H15") (pin "2") (pinfunction "2_2") (pintype "unspecified"))
      (node (ref "H19") (pin "6") (pinfunction "6_6") (pintype "unspecified"))
    )
    (net (code "16") (name "/UART0TX") (class "Default")
      (node (ref "H15") (pin "3") (pinfunction "3_3") (pintype "unspecified"))
      (node (ref "H19") (pin "4") (pinfunction "4_4") (pintype "unspecified"))
    )
    (net (code "17") (name "/VCC3V3") (class "Default")
      (node (ref "C4") (pin "2") (pinfunction "2_2") (pintype "unspecified"))
      (node (ref "H1") (pin "5") (pinfunction "5_5") (pintype "unspecified"))
      (node (ref "H16") (pin "4") (pinfunction "4_4") (pintype "unspecified"))
      (node (ref "H2") (pin "5") (pinfunction "5_5") (pintype "unspecified"))
      (node (ref "H6") (pin "6") (pinfunction "6_6") (pintype "unspecified"))
      (node (ref "LED2") (pin "1") (pinfunction "A_1") (pintype "unspecified"))
      (node (ref "U14") (pin "2") (pinfunction "VOUT_2") (pintype "input"))
    )
    (net (code "18") (name "AD0") (class "Default")
      (node (ref "H12") (pin "2") (pinfunction "2_2") (pintype "unspecified"))
      (node (ref "H20") (pin "3") (pinfunction "3_3") (pintype "unspecified"))
    )
    (net (code "19") (name "AD1") (class "Default")
      (node (ref "H12") (pin "1") (pinfunction "1_1") (pintype "unspecified"))
      (node (ref "H20") (pin "5") (pinfunction "5_5") (pintype "unspecified"))
    )
    (net (code "20") (name "AD2") (class "Default")
      (node (ref "H13") (pin "4") (pinfunction "4_4") (pintype "unspecified"))
      (node (ref "H20") (pin "2") (pinfunction "2_2") (pintype "unspecified"))
    )
    (net (code "21") (name "AD3") (class "Default")
      (node (ref "H13") (pin "2") (pinfunction "2_2") (pintype "unspecified"))
      (node (ref "H20") (pin "6") (pinfunction "6_6") (pintype "unspecified"))
    )
    (net (code "22") (name "AD4") (class "Default")
      (node (ref "H12") (pin "3") (pinfunction "3_3") (pintype "unspecified"))
      (node (ref "H20") (pin "1") (pinfunction "1_1") (pintype "unspecified"))
    )
    (net (code "23") (name "AD5") (class "Default")
      (node (ref "H13") (pin "5") (pinfunction "5_5") (pintype "unspecified"))
      (node (ref "H20") (pin "7") (pinfunction "7_7") (pintype "unspecified"))
    )
    (net (code "24") (name "AD6") (class "Default")
      (node (ref "H13") (pin "3") (pinfunction "3_3") (pintype "unspecified"))
      (node (ref "H20") (pin "4") (pinfunction "4_4") (pintype "unspecified"))
    )
    (net (code "25") (name "AD7") (class "Default")
      (node (ref "H13") (pin "1") (pinfunction "1_1") (pintype "unspecified"))
      (node (ref "H20") (pin "8") (pinfunction "8_8") (pintype "unspecified"))
      (node (ref "R26") (pin "2") (pinfunction "2_2") (pintype "input"))
    )
    (net (code "26") (name "BAT") (class "Default")
      (node (ref "C14") (pin "2") (pinfunction "2_2") (pintype "unspecified"))
      (node (ref "C21") (pin "2") (pinfunction "2_2") (pintype "unspecified"))
      (node (ref "C5") (pin "1") (pinfunction "1_1") (pintype "unspecified"))
      (node (ref "C6") (pin "2") (pinfunction "2_2") (pintype "unspecified"))
      (node (ref "R11") (pin "2") (pinfunction "2_2") (pintype "unspecified"))
      (node (ref "R18") (pin "2") (pinfunction "2_2") (pintype "unspecified"))
      (node (ref "R27") (pin "2") (pinfunction "2_2") (pintype "unspecified"))
      (node (ref "SW1") (pin "1") (pinfunction "1_1") (pintype "input"))
      (node (ref "U16") (pin "2") (pinfunction "VIN_2") (pintype "unspecified"))
      (node (ref "U17") (pin "2") (pinfunction "VIN_2") (pintype "unspecified"))
      (node (ref "U18") (pin "2") (pinfunction "VIN_2") (pintype "unspecified"))
    )
    (net (code "27") (name "GND") (class "Default")
      (node (ref "C10") (pin "1") (pinfunction "1_1") (pintype "input"))
      (node (ref "C12") (pin "2") (pinfunction "2_2") (pintype "unspecified"))
      (node (ref "C14") (pin "1") (pinfunction "1_1") (pintype "unspecified"))
      (node (ref "C18") (pin "1") (pinfunction "1_1") (pintype "input"))
      (node (ref "C20") (pin "2") (pinfunction "2_2") (pintype "unspecified"))
      (node (ref "C21") (pin "1") (pinfunction "1_1") (pintype "unspecified"))
      (node (ref "C25") (pin "1") (pinfunction "1_1") (pintype "input"))
      (node (ref "C27") (pin "2") (pinfunction "2_2") (pintype "unspecified"))
      (node (ref "C28") (pin "1") (pinfunction "1_1") (pintype "input"))
      (node (ref "C29") (pin "1") (pinfunction "1_1") (pintype "input"))
      (node (ref "C3") (pin "2") (pinfunction "2_2") (pintype "input"))
      (node (ref "C30") (pin "1") (pinfunction "1_1") (pintype "input"))
      (node (ref "C31") (pin "2") (pinfunction "2_2") (pintype "input"))
      (node (ref "C32") (pin "2") (pinfunction "2_2") (pintype "input"))
      (node (ref "C33") (pin "2") (pinfunction "2_2") (pintype "input"))
      (node (ref "C4") (pin "1") (pinfunction "1_1") (pintype "unspecified"))
      (node (ref "C5") (pin "2") (pinfunction "2_2") (pintype "unspecified"))
      (node (ref "C6") (pin "1") (pinfunction "1_1") (pintype "unspecified"))
      (node (ref "CN1") (pin "1") (pinfunction "1_1") (pintype "unspecified"))
      (node (ref "D11") (pin "2") (pinfunction "2_2") (pintype "unspecified"))
      (node (ref "D12") (pin "2") (pinfunction "2_2") (pintype "unspecified"))
      (node (ref "D13") (pin "2") (pinfunction "2_2") (pintype "unspecified"))
      (node (ref "D7") (pin "1") (pinfunction "A_1") (pintype "unspecified"))
      (node (ref "H1") (pin "6") (pinfunction "6_6") (pintype "unspecified"))
      (node (ref "H12") (pin "4") (pinfunction "4_4") (pintype "unspecified"))
      (node (ref "H14") (pin "2") (pinfunction "2_2") (pintype "unspecified"))
      (node (ref "H14") (pin "4") (pinfunction "4_4") (pintype "unspecified"))
      (node (ref "H14") (pin "6") (pinfunction "6_6") (pintype "unspecified"))
      (node (ref "H14") (pin "8") (pinfunction "8_8") (pintype "unspecified"))
      (node (ref "H15") (pin "1") (pinfunction "1_1") (pintype "unspecified"))
      (node (ref "H16") (pin "3") (pinfunction "3_3") (pintype "unspecified"))
      (node (ref "H17") (pin "1") (pinfunction "1_1") (pintype "unspecified"))
      (node (ref "H18") (pin "2") (pinfunction "2_2") (pintype "unspecified"))
      (node (ref "H19") (pin "1") (pinfunction "1_1") (pintype "unspecified"))
      (node (ref "H19") (pin "19") (pinfunction "19_19") (pintype "unspecified"))
      (node (ref "H19") (pin "20") (pinfunction "20_20") (pintype "unspecified"))
      (node (ref "H19") (pin "29") (pinfunction "29_29") (pintype "unspecified"))
      (node (ref "H2") (pin "6") (pinfunction "6_6") (pintype "unspecified"))
      (node (ref "H3") (pin "1") (pinfunction "1_1") (pintype "unspecified"))
      (node (ref "H4") (pin "1") (pinfunction "1_1") (pintype "unspecified"))
      (node (ref "H6") (pin "1") (pinfunction "1_1") (pintype "unspecified"))
      (node (ref "LED1") (pin "2") (pinfunction "K_2") (pintype "unspecified"))
      (node (ref "LED5") (pin "2") (pinfunction "K_2") (pintype "unspecified"))
      (node (ref "R12") (pin "1") (pinfunction "1_1") (pintype "unspecified"))
      (node (ref "R15") (pin "2") (pinfunction "2_2") (pintype "unspecified"))
      (node (ref "R19") (pin "1") (pinfunction "1_1") (pintype "unspecified"))
      (node (ref "R28") (pin "1") (pinfunction "1_1") (pintype "unspecified"))
      (node (ref "R34") (pin "2") (pinfunction "2_2") (pintype "unspecified"))
      (node (ref "R35") (pin "2") (pinfunction "2_2") (pintype "input"))
      (node (ref "R36") (pin "2") (pinfunction "2_2") (pintype "input"))
      (node (ref "R37") (pin "2") (pinfunction "2_2") (pintype "input"))
      (node (ref "R38") (pin "2") (pinfunction "2_2") (pintype "input"))
      (node (ref "R39") (pin "2") (pinfunction "2_2") (pintype "input"))
      (node (ref "R42") (pin "1") (pinfunction "1_1") (pintype "unspecified"))
      (node (ref "R43") (pin "1") (pinfunction "1_1") (pintype "unspecified"))
      (node (ref "R44") (pin "2") (pinfunction "2_2") (pintype "unspecified"))
      (node (ref "R45") (pin "2") (pinfunction "2_2") (pintype "unspecified"))
      (node (ref "U14") (pin "1") (pinfunction "ADJ/GND_1") (pintype "input"))
      (node (ref "U15") (pin "1") (pinfunction "-_1") (pintype "unspecified"))
      (node (ref "U16") (pin "7") (pinfunction "GND_7") (pintype "unspecified"))
      (node (ref "U17") (pin "7") (pinfunction "GND_7") (pintype "unspecified"))
      (node (ref "U18") (pin "7") (pinfunction "GND_7") (pintype "unspecified"))
      (node (ref "U19") (pin "2") (pinfunction "2_2") (pintype "unspecified"))
    )
    (net (code "28") (name "IO88") (class "Default")
      (node (ref "D7") (pin "3") (pinfunction "C_3") (pintype "unspecified"))
      (node (ref "H19") (pin "3") (pinfunction "3_3") (pintype "unspecified"))
      (node (ref "R17") (pin "1") (pinfunction "1_1") (pintype "input"))
    )
    (net (code "29") (name "Net-(C9-Pad1)") (class "Default")
      (node (ref "C9") (pin "1") (pinfunction "1_1") (pintype "input"))
      (node (ref "R42") (pin "2") (pinfunction "2_2") (pintype "unspecified"))
    )
    (net (code "30") (name "Net-(C17-Pad1)") (class "Default")
      (node (ref "C17") (pin "1") (pinfunction "1_1") (pintype "input"))
      (node (ref "R44") (pin "1") (pinfunction "1_1") (pintype "unspecified"))
    )
    (net (code "31") (name "Net-(C24-Pad1)") (class "Default")
      (node (ref "C24") (pin "1") (pinfunction "1_1") (pintype "input"))
      (node (ref "R43") (pin "2") (pinfunction "2_2") (pintype "unspecified"))
    )
    (net (code "32") (name "Net-(H17-Pad3)") (class "Default")
      (node (ref "H17") (pin "3") (pinfunction "3_3") (pintype "unspecified"))
      (node (ref "R17") (pin "2") (pinfunction "2_2") (pintype "input"))
    )
    (net (code "33") (name "Net-(H18-Pad1)") (class "Default")
      (node (ref "H18") (pin "1") (pinfunction "1_1") (pintype "unspecified"))
      (node (ref "R26") (pin "1") (pinfunction "1_1") (pintype "input"))
    )
    (net (code "34") (name "Net-(LED1-A)") (class "Default")
      (node (ref "LED1") (pin "1") (pinfunction "A_1") (pintype "unspecified"))
      (node (ref "R16") (pin "1") (pinfunction "1_1") (pintype "unspecified"))
    )
    (net (code "35") (name "Net-(LED2-K)") (class "Default")
      (node (ref "LED2") (pin "2") (pinfunction "K_2") (pintype "unspecified"))
      (node (ref "U19") (pin "1") (pinfunction "1_1") (pintype "unspecified"))
    )
    (net (code "36") (name "Net-(LED3-K)") (class "Default")
      (node (ref "LED3") (pin "2") (pinfunction "K_2") (pintype "unspecified"))
      (node (ref "R35") (pin "1") (pinfunction "1_1") (pintype "input"))
    )
    (net (code "37") (name "Net-(LED5-A)") (class "Default")
      (node (ref "LED5") (pin "1") (pinfunction "A_1") (pintype "unspecified"))
      (node (ref "R25") (pin "2") (pinfunction "2_2") (pintype "input"))
    )
    (net (code "38") (name "Net-(U15-+)") (class "Default")
      (node (ref "SW1") (pin "2") (pinfunction "2_2") (pintype "input"))
      (node (ref "U15") (pin "2") (pinfunction "+_2") (pintype "unspecified"))
    )
    (net (code "39") (name "Net-(U16-BOOT)") (class "Default")
      (node (ref "C8") (pin "2") (pinfunction "2_2") (pintype "unspecified"))
      (node (ref "U16") (pin "1") (pinfunction "BOOT_1") (pintype "unspecified"))
    )
    (net (code "40") (name "Net-(U16-COMP)") (class "Default")
      (node (ref "C10") (pin "2") (pinfunction "2_2") (pintype "input"))
      (node (ref "C9") (pin "2") (pinfunction "2_2") (pintype "input"))
      (node (ref "U16") (pin "6") (pinfunction "COMP_6") (pintype "unspecified"))
    )
    (net (code "41") (name "Net-(U16-EN)") (class "Default")
      (node (ref "R11") (pin "1") (pinfunction "1_1") (pintype "unspecified"))
      (node (ref "R12") (pin "2") (pinfunction "2_2") (pintype "unspecified"))
      (node (ref "U16") (pin "3") (pinfunction "EN_3") (pintype "unspecified"))
    )
    (net (code "42") (name "Net-(U16-PH)") (class "Default")
      (node (ref "C8") (pin "1") (pinfunction "1_1") (pintype "unspecified"))
      (node (ref "D13") (pin "1") (pinfunction "1_1") (pintype "unspecified"))
      (node (ref "L1") (pin "1") (pinfunction "1_1") (pintype "unspecified"))
      (node (ref "U16") (pin "8") (pinfunction "PH_8") (pintype "unspecified"))
    )
    (net (code "43") (name "Net-(U16-SS)") (class "Default")
      (node (ref "C30") (pin "2") (pinfunction "2_2") (pintype "input"))
      (node (ref "U16") (pin "4") (pinfunction "SS_4") (pintype "unspecified"))
    )
    (net (code "44") (name "Net-(U16-VSENSE)") (class "Default")
      (node (ref "R14") (pin "1") (pinfunction "1_1") (pintype "input"))
      (node (ref "R15") (pin "1") (pinfunction "1_1") (pintype "unspecified"))
      (node (ref "U16") (pin "5") (pinfunction "VSENSE_5") (pintype "unspecified"))
    )
    (net (code "45") (name "Net-(U17-BOOT)") (class "Default")
      (node (ref "C16") (pin "2") (pinfunction "2_2") (pintype "unspecified"))
      (node (ref "U17") (pin "1") (pinfunction "BOOT_1") (pintype "unspecified"))
    )
    (net (code "46") (name "Net-(U17-COMP)") (class "Default")
      (node (ref "C17") (pin "2") (pinfunction "2_2") (pintype "input"))
      (node (ref "C18") (pin "2") (pinfunction "2_2") (pintype "input"))
      (node (ref "U17") (pin "6") (pinfunction "COMP_6") (pintype "unspecified"))
    )
    (net (code "47") (name "Net-(U17-EN)") (class "Default")
      (node (ref "R18") (pin "1") (pinfunction "1_1") (pintype "unspecified"))
      (node (ref "R19") (pin "2") (pinfunction "2_2") (pintype "unspecified"))
      (node (ref "U17") (pin "3") (pinfunction "EN_3") (pintype "unspecified"))
    )
    (net (code "48") (name "Net-(U17-PH)") (class "Default")
      (node (ref "C16") (pin "1") (pinfunction "1_1") (pintype "unspecified"))
      (node (ref "D11") (pin "1") (pinfunction "1_1") (pintype "unspecified"))
      (node (ref "L2") (pin "1") (pinfunction "1_1") (pintype "unspecified"))
      (node (ref "U17") (pin "8") (pinfunction "PH_8") (pintype "unspecified"))
    )
    (net (code "49") (name "Net-(U17-SS)") (class "Default")
      (node (ref "C28") (pin "2") (pinfunction "2_2") (pintype "input"))
      (node (ref "U17") (pin "4") (pinfunction "SS_4") (pintype "unspecified"))
    )
    (net (code "50") (name "Net-(U17-VSENSE)") (class "Default")
      (node (ref "R21") (pin "2") (pinfunction "2_2") (pintype "input"))
      (node (ref "R45") (pin "1") (pinfunction "1_1") (pintype "unspecified"))
      (node (ref "U17") (pin "5") (pinfunction "VSENSE_5") (pintype "unspecified"))
    )
    (net (code "51") (name "Net-(U18-BOOT)") (class "Default")
      (node (ref "C23") (pin "2") (pinfunction "2_2") (pintype "unspecified"))
      (node (ref "U18") (pin "1") (pinfunction "BOOT_1") (pintype "unspecified"))
    )
    (net (code "52") (name "Net-(U18-COMP)") (class "Default")
      (node (ref "C24") (pin "2") (pinfunction "2_2") (pintype "input"))
      (node (ref "C25") (pin "2") (pinfunction "2_2") (pintype "input"))
      (node (ref "U18") (pin "6") (pinfunction "COMP_6") (pintype "unspecified"))
    )
    (net (code "53") (name "Net-(U18-EN)") (class "Default")
      (node (ref "R27") (pin "1") (pinfunction "1_1") (pintype "unspecified"))
      (node (ref "R28") (pin "2") (pinfunction "2_2") (pintype "unspecified"))
      (node (ref "U18") (pin "3") (pinfunction "EN_3") (pintype "unspecified"))
    )
    (net (code "54") (name "Net-(U18-PH)") (class "Default")
      (node (ref "C23") (pin "1") (pinfunction "1_1") (pintype "unspecified"))
      (node (ref "D12") (pin "1") (pinfunction "1_1") (pintype "unspecified"))
      (node (ref "L3") (pin "1") (pinfunction "1_1") (pintype "unspecified"))
      (node (ref "U18") (pin "8") (pinfunction "PH_8") (pintype "unspecified"))
    )
    (net (code "55") (name "Net-(U18-SS)") (class "Default")
      (node (ref "C29") (pin "2") (pinfunction "2_2") (pintype "input"))
      (node (ref "U18") (pin "4") (pinfunction "SS_4") (pintype "unspecified"))
    )
    (net (code "56") (name "Net-(U18-VSENSE)") (class "Default")
      (node (ref "R34") (pin "1") (pinfunction "1_1") (pintype "unspecified"))
      (node (ref "R41") (pin "1") (pinfunction "1_1") (pintype "unspecified"))
      (node (ref "U18") (pin "5") (pinfunction "VSENSE_5") (pintype "unspecified"))
    )
    (net (code "57") (name "VADJ") (class "Default")
      (node (ref "C12") (pin "1") (pinfunction "1_1") (pintype "unspecified"))
      (node (ref "C31") (pin "1") (pinfunction "1_1") (pintype "input"))
      (node (ref "H17") (pin "2") (pinfunction "2_2") (pintype "unspecified"))
      (node (ref "H3") (pin "2") (pinfunction "2_2") (pintype "unspecified"))
      (node (ref "H4") (pin "2") (pinfunction "2_2") (pintype "unspecified"))
      (node (ref "L1") (pin "2") (pinfunction "2_2") (pintype "unspecified"))
      (node (ref "R14") (pin "2") (pinfunction "2_2") (pintype "input"))
      (node (ref "R16") (pin "2") (pinfunction "2_2") (pintype "unspecified"))
    )
    (net (code "58") (name "VCC5V") (class "Default")
      (node (ref "C20") (pin "1") (pinfunction "1_1") (pintype "unspecified"))
      (node (ref "C3") (pin "1") (pinfunction "1_1") (pintype "input"))
      (node (ref "C32") (pin "1") (pinfunction "1_1") (pintype "input"))
      (node (ref "H14") (pin "1") (pinfunction "1_1") (pintype "unspecified"))
      (node (ref "H14") (pin "3") (pinfunction "3_3") (pintype "unspecified"))
      (node (ref "H14") (pin "5") (pinfunction "5_5") (pintype "unspecified"))
      (node (ref "H14") (pin "7") (pinfunction "7_7") (pintype "unspecified"))
      (node (ref "H18") (pin "3") (pinfunction "3_3") (pintype "unspecified"))
      (node (ref "H19") (pin "30") (pinfunction "30_30") (pintype "unspecified"))
      (node (ref "L2") (pin "2") (pinfunction "2_2") (pintype "unspecified"))
      (node (ref "R21") (pin "1") (pinfunction "1_1") (pintype "input"))
      (node (ref "R25") (pin "1") (pinfunction "1_1") (pintype "input"))
      (node (ref "U14") (pin "3") (pinfunction "VIN_3") (pintype "input"))
    )
    (net (code "59") (name "VCC7.2V") (class "Default")
      (node (ref "C27") (pin "1") (pinfunction "1_1") (pintype "unspecified"))
      (node (ref "C33") (pin "1") (pinfunction "1_1") (pintype "input"))
      (node (ref "CN1") (pin "2") (pinfunction "2_2") (pintype "unspecified"))
      (node (ref "L3") (pin "2") (pinfunction "2_2") (pintype "unspecified"))
      (node (ref "LED3") (pin "1") (pinfunction "A_1") (pintype "unspecified"))
      (node (ref "R41") (pin "2") (pinfunction "2_2") (pintype "unspecified"))
    )
    (net (code "60") (name "unconnected-(D7-NC-Pad2)") (class "Default")
      (node (ref "D7") (pin "2") (pinfunction "NC_2") (pintype "unspecified"))
    )
    (net (code "61") (name "unconnected-(H1-Pad1)") (class "Default")
      (node (ref "H1") (pin "1") (pinfunction "1_1") (pintype "unspecified+no_connect"))
    )
    (net (code "62") (name "unconnected-(H1-Pad2)") (class "Default")
      (node (ref "H1") (pin "2") (pinfunction "2_2") (pintype "unspecified+no_connect"))
    )
    (net (code "63") (name "unconnected-(H2-Pad1)") (class "Default")
      (node (ref "H2") (pin "1") (pinfunction "1_1") (pintype "unspecified+no_connect"))
    )
    (net (code "64") (name "unconnected-(H2-Pad2)") (class "Default")
      (node (ref "H2") (pin "2") (pinfunction "2_2") (pintype "unspecified+no_connect"))
    )
    (net (code "65") (name "unconnected-(H19-Pad12)") (class "Default")
      (node (ref "H19") (pin "12") (pinfunction "12_12") (pintype "unspecified+no_connect"))
    )
    (net (code "66") (name "unconnected-(H19-Pad14)") (class "Default")
      (node (ref "H19") (pin "14") (pinfunction "14_14") (pintype "unspecified+no_connect"))
    )
    (net (code "67") (name "unconnected-(H19-Pad16)") (class "Default")
      (node (ref "H19") (pin "16") (pinfunction "16_16") (pintype "unspecified+no_connect"))
    )
    (net (code "68") (name "unconnected-(H19-Pad18)") (class "Default")
      (node (ref "H19") (pin "18") (pinfunction "18_18") (pintype "unspecified+no_connect"))
    )
    (net (code "69") (name "unconnected-(H19-Pad22)") (class "Default")
      (node (ref "H19") (pin "22") (pinfunction "22_22") (pintype "unspecified+no_connect"))
    )
    (net (code "70") (name "unconnected-(H19-Pad24)") (class "Default")
      (node (ref "H19") (pin "24") (pinfunction "24_24") (pintype "unspecified+no_connect"))
    )
    (net (code "71") (name "unconnected-(H19-Pad26)") (class "Default")
      (node (ref "H19") (pin "26") (pinfunction "26_26") (pintype "unspecified+no_connect"))
    )
    (net (code "72") (name "unconnected-(H19-Pad28)") (class "Default")
      (node (ref "H19") (pin "28") (pinfunction "28_28") (pintype "unspecified+no_connect"))
    )
    (net (code "73") (name "unconnected-(R15-Pad3)") (class "Default")
      (node (ref "R15") (pin "3") (pinfunction "3_3") (pintype "unspecified+no_connect"))
    )
    (net (code "74") (name "unconnected-(R34-Pad3)") (class "Default")
      (node (ref "R34") (pin "3") (pinfunction "3_3") (pintype "unspecified+no_connect"))
    )
    (net (code "75") (name "unconnected-(R45-Pad3)") (class "Default")
      (node (ref "R45") (pin "3") (pinfunction "3_3") (pintype "unspecified+no_connect"))
    )
  )
)
